# TB01.net
KiCad netlist of a schematic drawn in EAGLE
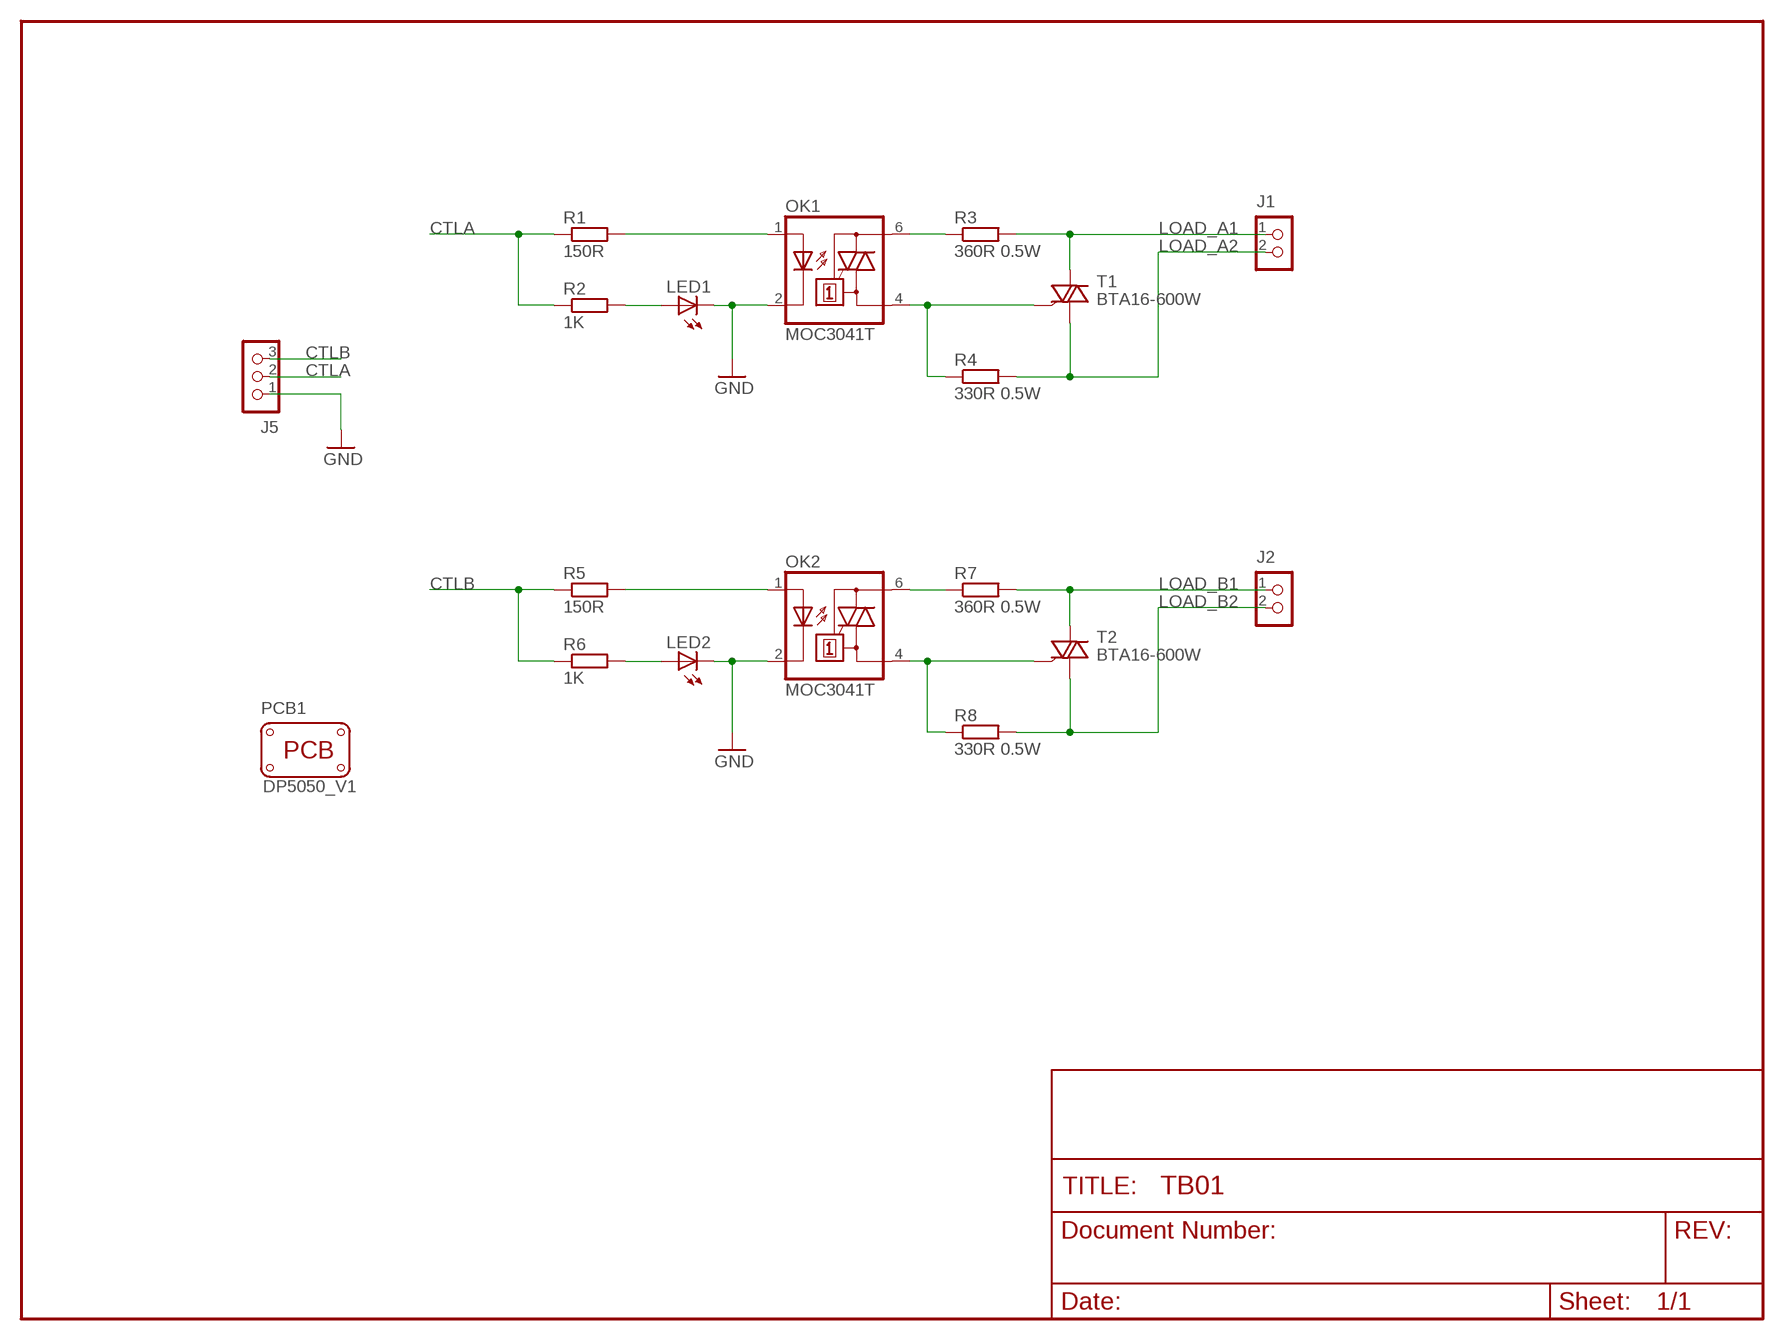
[diagram p0: schematic, sheet 1]

(export (version "E")
  (design (tool "Eeschema 10.0.6"))
  (components
    (comp (ref "J1")
      (value "CON_TERMINAL_BLOCK_02-5MM")
      (footprint "eagle-import:TERMINAL_BLOCK_2P_5")
      (libsource (lib "eagle-import") (part "CON_TERMINAL_BLOCK_02-5MM"))
    )
    (comp (ref "J2")
      (value "CON_TERMINAL_BLOCK_02-5MM")
      (footprint "eagle-import:TERMINAL_BLOCK_2P_5")
      (libsource (lib "eagle-import") (part "CON_TERMINAL_BLOCK_02-5MM"))
    )
    (comp (ref "J5")
      (value "CON_TERMINAL_BLOCK_03-5MM")
      (footprint "eagle-import:TERMINAL_BLOCK_3P_5")
      (libsource (lib "eagle-import") (part "CON_TERMINAL_BLOCK_03-5MM"))
    )
    (comp (ref "LED1")
      (value "LED3MM")
      (footprint "eagle-import:LED3MM")
      (libsource (lib "eagle-import") (part "LED3MM"))
    )
    (comp (ref "LED2")
      (value "LED3MM")
      (footprint "eagle-import:LED3MM")
      (libsource (lib "eagle-import") (part "LED3MM"))
    )
    (comp (ref "OK1")
      (value "MOC3041T")
      (footprint "eagle-import:DIL06B")
      (libsource (lib "eagle-import") (part "MOC30T41"))
    )
    (comp (ref "OK2")
      (value "MOC3041T")
      (footprint "eagle-import:DIL06B")
      (libsource (lib "eagle-import") (part "MOC30T41"))
    )
    (comp (ref "PCB1")
      (value "PCB_DP_SQUARE-5X5")
      (footprint "eagle-import:DP5050_V1")
      (libsource (lib "eagle-import") (part "PCB_DP_SQUARE-5X5"))
    )
    (comp (ref "R1")
      (value "150R")
      (footprint "eagle-import:0207_7")
      (libsource (lib "eagle-import") (part "R-EU_0207/7"))
    )
    (comp (ref "R2")
      (value "1K")
      (footprint "eagle-import:0207_7")
      (libsource (lib "eagle-import") (part "R-EU_0207/7"))
    )
    (comp (ref "R3")
      (value "360R 0.5W")
      (footprint "eagle-import:0411V")
      (libsource (lib "eagle-import") (part "R-EU_0411/3V"))
    )
    (comp (ref "R4")
      (value "330R 0.5W")
      (footprint "eagle-import:0411V")
      (libsource (lib "eagle-import") (part "R-EU_0411/3V"))
    )
    (comp (ref "R5")
      (value "150R")
      (footprint "eagle-import:0207_7")
      (libsource (lib "eagle-import") (part "R-EU_0207/7"))
    )
    (comp (ref "R6")
      (value "1K")
      (footprint "eagle-import:0207_7")
      (libsource (lib "eagle-import") (part "R-EU_0207/7"))
    )
    (comp (ref "R7")
      (value "360R 0.5W")
      (footprint "eagle-import:0411V")
      (libsource (lib "eagle-import") (part "R-EU_0411/3V"))
    )
    (comp (ref "R8")
      (value "330R 0.5W")
      (footprint "eagle-import:0411V")
      (libsource (lib "eagle-import") (part "R-EU_0411/3V"))
    )
    (comp (ref "T1")
      (value "BTA16-600W")
      (footprint "eagle-import:TO220DSH")
      (libsource (lib "eagle-import") (part "BT138"))
    )
    (comp (ref "T2")
      (value "BTA16-600W")
      (footprint "eagle-import:TO220DSH")
      (libsource (lib "eagle-import") (part "BT138"))
    )
  )
  (nets
    (net (code "1") (name "/CTLA") (class "Default")
      (node (ref "J5") (pin "2") (pinfunction "2_2") (pintype "bidirectional"))
      (node (ref "R1") (pin "1") (pinfunction "1_1") (pintype "passive"))
      (node (ref "R2") (pin "1") (pinfunction "1_1") (pintype "passive"))
    )
    (net (code "2") (name "/CTLB") (class "Default")
      (node (ref "J5") (pin "3") (pinfunction "3_3") (pintype "bidirectional"))
      (node (ref "R5") (pin "1") (pinfunction "1_1") (pintype "passive"))
      (node (ref "R6") (pin "1") (pinfunction "1_1") (pintype "passive"))
    )
    (net (code "3") (name "/LOAD_A1") (class "Default")
      (node (ref "J1") (pin "1") (pinfunction "1_1") (pintype "passive"))
      (node (ref "R3") (pin "2") (pinfunction "2_2") (pintype "passive"))
      (node (ref "T1") (pin "A2") (pinfunction "A2_A2") (pintype "passive"))
    )
    (net (code "4") (name "/LOAD_A2") (class "Default")
      (node (ref "J1") (pin "2") (pinfunction "2_2") (pintype "passive"))
      (node (ref "R4") (pin "2") (pinfunction "2_2") (pintype "passive"))
      (node (ref "T1") (pin "A1") (pinfunction "A1_A1") (pintype "passive"))
    )
    (net (code "5") (name "/LOAD_B1") (class "Default")
      (node (ref "J2") (pin "1") (pinfunction "1_1") (pintype "passive"))
      (node (ref "R7") (pin "2") (pinfunction "2_2") (pintype "passive"))
      (node (ref "T2") (pin "A2") (pinfunction "A2_A2") (pintype "passive"))
    )
    (net (code "6") (name "/LOAD_B2") (class "Default")
      (node (ref "J2") (pin "2") (pinfunction "2_2") (pintype "passive"))
      (node (ref "R8") (pin "2") (pinfunction "2_2") (pintype "passive"))
      (node (ref "T2") (pin "A1") (pinfunction "A1_A1") (pintype "passive"))
    )
    (net (code "7") (name "GND") (class "Default")
      (node (ref "J5") (pin "1") (pinfunction "1_1") (pintype "bidirectional"))
      (node (ref "LED1") (pin "K") (pinfunction "C_K") (pintype "passive"))
      (node (ref "LED2") (pin "K") (pinfunction "C_K") (pintype "passive"))
      (node (ref "OK1") (pin "2") (pinfunction "C_2") (pintype "passive"))
      (node (ref "OK2") (pin "2") (pinfunction "C_2") (pintype "passive"))
    )
    (net (code "8") (name "Net-(LED1-PadA)") (class "Default")
      (node (ref "LED1") (pin "A") (pinfunction "A_A") (pintype "passive"))
      (node (ref "R2") (pin "2") (pinfunction "2_2") (pintype "passive"))
    )
    (net (code "9") (name "Net-(LED2-PadA)") (class "Default")
      (node (ref "LED2") (pin "A") (pinfunction "A_A") (pintype "passive"))
      (node (ref "R6") (pin "2") (pinfunction "2_2") (pintype "passive"))
    )
    (net (code "10") (name "Net-(OK1-A)") (class "Default")
      (node (ref "OK1") (pin "1") (pinfunction "A_1") (pintype "passive"))
      (node (ref "R1") (pin "2") (pinfunction "2_2") (pintype "passive"))
    )
    (net (code "11") (name "Net-(OK1-A1)") (class "Default")
      (node (ref "OK1") (pin "4") (pinfunction "A1_4") (pintype "passive"))
      (node (ref "R4") (pin "1") (pinfunction "1_1") (pintype "passive"))
      (node (ref "T1") (pin "G") (pinfunction "G_G") (pintype "passive"))
    )
    (net (code "12") (name "Net-(OK1-A2)") (class "Default")
      (node (ref "OK1") (pin "6") (pinfunction "A2_6") (pintype "passive"))
      (node (ref "R3") (pin "1") (pinfunction "1_1") (pintype "passive"))
    )
    (net (code "13") (name "Net-(OK2-A)") (class "Default")
      (node (ref "OK2") (pin "1") (pinfunction "A_1") (pintype "passive"))
      (node (ref "R5") (pin "2") (pinfunction "2_2") (pintype "passive"))
    )
    (net (code "14") (name "Net-(OK2-A1)") (class "Default")
      (node (ref "OK2") (pin "4") (pinfunction "A1_4") (pintype "passive"))
      (node (ref "R8") (pin "1") (pinfunction "1_1") (pintype "passive"))
      (node (ref "T2") (pin "G") (pinfunction "G_G") (pintype "passive"))
    )
    (net (code "15") (name "Net-(OK2-A2)") (class "Default")
      (node (ref "OK2") (pin "6") (pinfunction "A2_6") (pintype "passive"))
      (node (ref "R7") (pin "1") (pinfunction "1_1") (pintype "passive"))
    )
  )
)
